# project_flashing_light.net
KiCad netlist of a schematic drawn in EAGLE
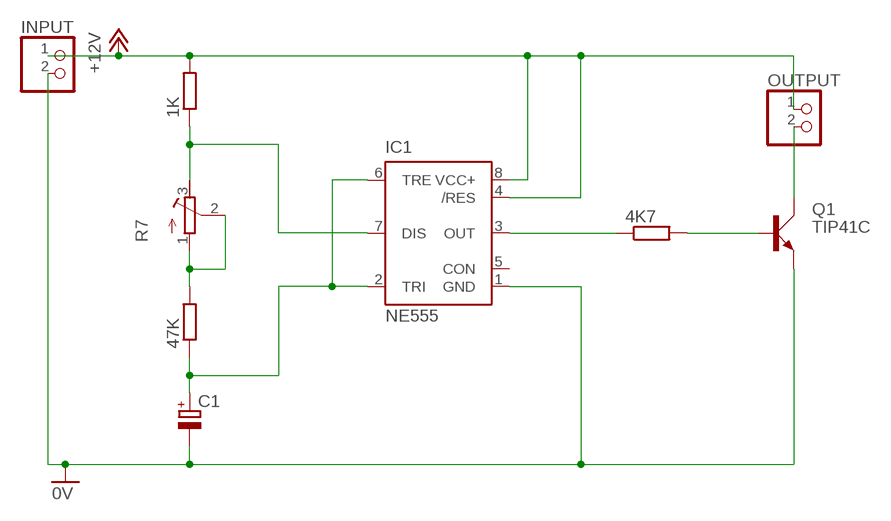
[diagram p0: schematic, sheet 1]

(export (version "E")
  (design (tool "Eeschema 10.0.6"))
  (components
    (comp (ref "1K")
      (value "R-EU_0207/15")
      (footprint "eagle-import:0207_15")
      (libsource (lib "eagle-import") (part "R-EU_0207/15"))
    )
    (comp (ref "4K7")
      (value "R-EU_0207/15")
      (footprint "eagle-import:0207_15")
      (libsource (lib "eagle-import") (part "R-EU_0207/15"))
    )
    (comp (ref "47K")
      (value "R-EU_0207/15")
      (footprint "eagle-import:0207_15")
      (libsource (lib "eagle-import") (part "R-EU_0207/15"))
    )
    (comp (ref "C1")
      (value "CPOL-EUE2.5-6")
      (footprint "eagle-import:E2,5-6")
      (libsource (lib "eagle-import") (part "CPOL-EUE2.5-6"))
    )
    (comp (ref "IC1")
      (value "NE555")
      (footprint "eagle-import:DIL-08")
      (fields (field (name "MF") "Arrow Electronics") (field (name "MPN") "NE555N"))
      (libsource (lib "eagle-import") (part "NE555"))
    )
    (comp (ref "INPUT")
      (value "PINHD-1X2")
      (footprint "eagle-import:1X02")
      (libsource (lib "eagle-import") (part "PINHD-1X2"))
    )
    (comp (ref "OUTPUT")
      (value "PINHD-1X2")
      (footprint "eagle-import:1X02")
      (libsource (lib "eagle-import") (part "PINHD-1X2"))
    )
    (comp (ref "Q1")
      (value "TIP41C")
      (footprint "eagle-import:TO220AV")
      (libsource (lib "eagle-import") (part "TIP41C"))
    )
    (comp (ref "R7")
      (value "R-TRIMM3339P")
      (footprint "eagle-import:RTRIM3339P")
      (libsource (lib "eagle-import") (part "R-TRIMM3339P"))
    )
  )
  (nets
    (net (code "1") (name "+12V") (class "Default")
      (node (ref "1K") (pin "2") (pinfunction "2_2") (pintype "passive"))
      (node (ref "IC1") (pin "4") (pinfunction "/RES_4") (pintype "input"))
      (node (ref "IC1") (pin "8") (pinfunction "VCC+_8") (pintype "power_in"))
      (node (ref "INPUT") (pin "1") (pinfunction "1_1") (pintype "passive"))
      (node (ref "OUTPUT") (pin "1") (pinfunction "1_1") (pintype "passive"))
    )
    (net (code "2") (name "0V") (class "Default")
      (node (ref "C1") (pin "-") (pinfunction "-_-") (pintype "passive"))
      (node (ref "IC1") (pin "1") (pinfunction "GND_1") (pintype "power_in"))
      (node (ref "INPUT") (pin "2") (pinfunction "2_2") (pintype "passive"))
      (node (ref "Q1") (pin "E") (pinfunction "E_E") (pintype "passive"))
    )
    (net (code "3") (name "Net-(4K7-Pad2)") (class "Default")
      (node (ref "4K7") (pin "2") (pinfunction "2_2") (pintype "passive"))
      (node (ref "Q1") (pin "B") (pinfunction "B_B") (pintype "passive"))
    )
    (net (code "4") (name "Net-(IC1-DIS)") (class "Default")
      (node (ref "1K") (pin "1") (pinfunction "1_1") (pintype "passive"))
      (node (ref "IC1") (pin "7") (pinfunction "DIS_7") (pintype "input"))
      (node (ref "R7") (pin "3") (pinfunction "E_3") (pintype "passive"))
    )
    (net (code "5") (name "Net-(IC1-OUT)") (class "Default")
      (node (ref "4K7") (pin "1") (pinfunction "1_1") (pintype "passive"))
      (node (ref "IC1") (pin "3") (pinfunction "OUT_3") (pintype "output"))
    )
    (net (code "6") (name "Net-(IC1-TRE)") (class "Default")
      (node (ref "47K") (pin "1") (pinfunction "1_1") (pintype "passive"))
      (node (ref "C1") (pin "+") (pinfunction "+_+") (pintype "passive"))
      (node (ref "IC1") (pin "2") (pinfunction "TRI_2") (pintype "input"))
      (node (ref "IC1") (pin "6") (pinfunction "TRE_6") (pintype "input"))
    )
    (net (code "7") (name "Net-(OUTPUT-Pad2)") (class "Default")
      (node (ref "OUTPUT") (pin "2") (pinfunction "2_2") (pintype "passive"))
      (node (ref "Q1") (pin "C") (pinfunction "C_C") (pintype "passive"))
    )
    (net (code "8") (name "Net-(R7-A)") (class "Default")
      (node (ref "47K") (pin "2") (pinfunction "2_2") (pintype "passive"))
      (node (ref "R7") (pin "1") (pinfunction "A_1") (pintype "passive"))
      (node (ref "R7") (pin "2") (pinfunction "S_2") (pintype "passive"))
    )
    (net (code "9") (name "unconnected-(IC1-CON-Pad5)") (class "Default")
      (node (ref "IC1") (pin "5") (pinfunction "CON_5") (pintype "input"))
    )
  )
)
